# SparkFun-XBee-Serial-Explorer-v12.net
KiCad netlist of a schematic drawn in EAGLE
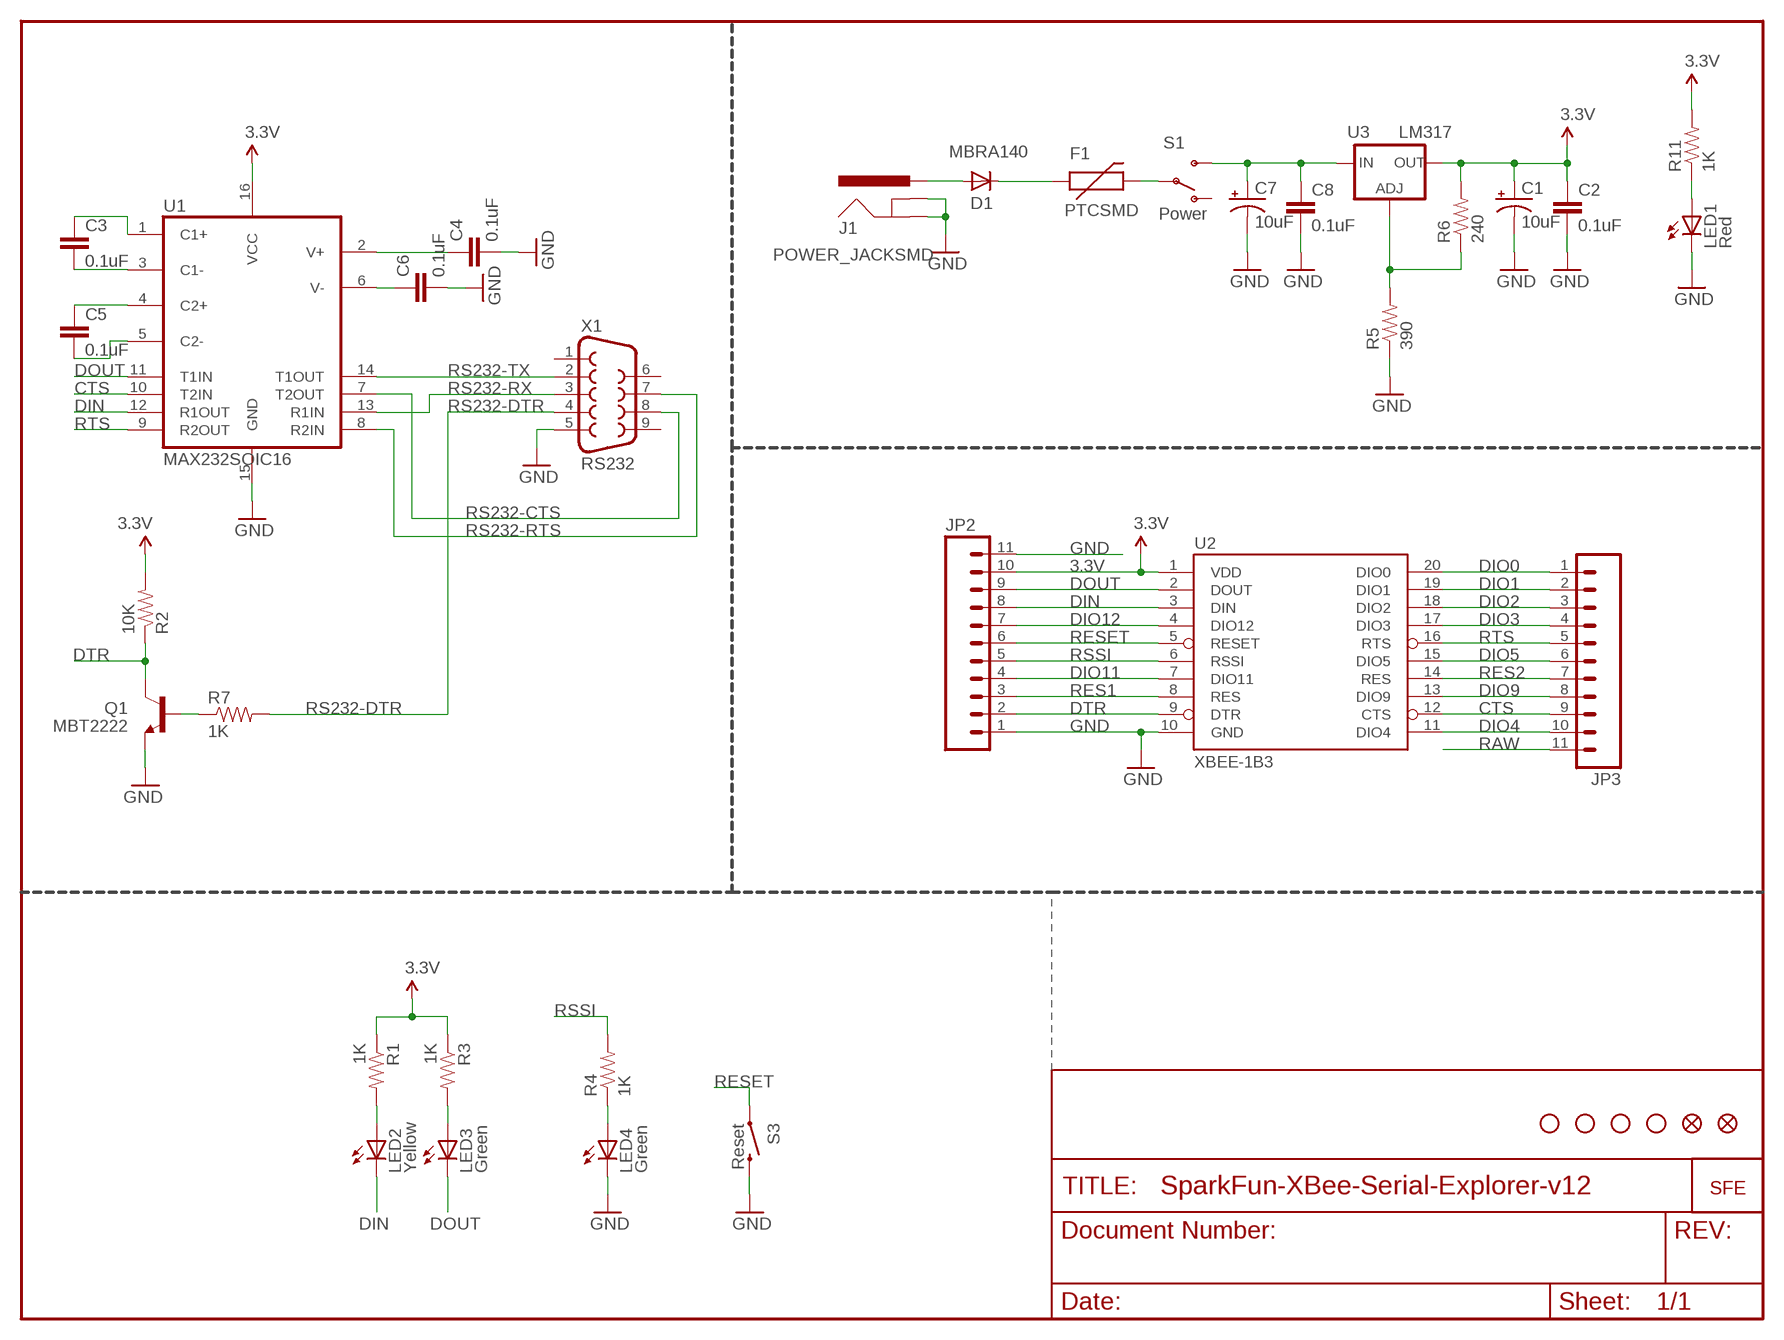
[diagram p0: schematic, sheet 1]

(export (version "E")
  (design (tool "Eeschema 10.0.6"))
  (components
    (comp (ref "C1")
      (value "10uF")
      (footprint "eagle-import:EIA3216")
      (libsource (lib "eagle-import") (part "CAP_POL1206"))
    )
    (comp (ref "C2")
      (value "0.1uF")
      (footprint "eagle-import:C0402")
      (libsource (lib "eagle-import") (part "CAP0402"))
    )
    (comp (ref "C3")
      (value "0.1uF")
      (footprint "eagle-import:C0402")
      (libsource (lib "eagle-import") (part "CAP0402"))
    )
    (comp (ref "C4")
      (value "0.1uF")
      (footprint "eagle-import:C0402")
      (libsource (lib "eagle-import") (part "CAP0402"))
    )
    (comp (ref "C5")
      (value "0.1uF")
      (footprint "eagle-import:C0402")
      (libsource (lib "eagle-import") (part "CAP0402"))
    )
    (comp (ref "C6")
      (value "0.1uF")
      (footprint "eagle-import:C0402")
      (libsource (lib "eagle-import") (part "CAP0402"))
    )
    (comp (ref "C7")
      (value "10uF")
      (footprint "eagle-import:EIA3216")
      (libsource (lib "eagle-import") (part "CAP_POL1206"))
    )
    (comp (ref "C8")
      (value "0.1uF")
      (footprint "eagle-import:C0402")
      (libsource (lib "eagle-import") (part "CAP0402"))
    )
    (comp (ref "D1")
      (value "MBRA140")
      (footprint "eagle-import:SMA-DIODE")
      (libsource (lib "eagle-import") (part "DIODESMA"))
    )
    (comp (ref "F1")
      (value "PTCSMD")
      (footprint "eagle-import:PTC-1206")
      (libsource (lib "eagle-import") (part "PTCSMD"))
    )
    (comp (ref "J1")
      (value "POWER_JACKSMD")
      (footprint "eagle-import:POWER_JACK_SMD")
      (libsource (lib "eagle-import") (part "POWER_JACKSMD"))
    )
    (comp (ref "JP2")
      (value "M11PTH")
      (footprint "eagle-import:1X11")
      (libsource (lib "eagle-import") (part "M11PTH"))
    )
    (comp (ref "JP3")
      (value "M11PTH")
      (footprint "eagle-import:1X11")
      (libsource (lib "eagle-import") (part "M11PTH"))
    )
    (comp (ref "LED1")
      (value "Red")
      (footprint "eagle-import:LED-1206")
      (libsource (lib "eagle-import") (part "LED1206"))
    )
    (comp (ref "LED2")
      (value "Yellow")
      (footprint "eagle-import:LED-1206")
      (libsource (lib "eagle-import") (part "LED1206"))
    )
    (comp (ref "LED3")
      (value "Green")
      (footprint "eagle-import:LED-1206")
      (libsource (lib "eagle-import") (part "LED1206"))
    )
    (comp (ref "LED4")
      (value "Green")
      (footprint "eagle-import:LED-1206")
      (libsource (lib "eagle-import") (part "LED1206"))
    )
    (comp (ref "Q1")
      (value "MBT2222")
      (footprint "eagle-import:SOT23-3")
      (libsource (lib "eagle-import") (part "TRANSISTOR_NPNSOT23-3"))
    )
    (comp (ref "R1")
      (value "1K")
      (footprint "eagle-import:C0402")
      (libsource (lib "eagle-import") (part "RESISTOR0402"))
    )
    (comp (ref "R2")
      (value "10K")
      (footprint "eagle-import:C0402")
      (libsource (lib "eagle-import") (part "RESISTOR0402"))
    )
    (comp (ref "R3")
      (value "1K")
      (footprint "eagle-import:C0402")
      (libsource (lib "eagle-import") (part "RESISTOR0402"))
    )
    (comp (ref "R4")
      (value "1K")
      (footprint "eagle-import:C0402")
      (libsource (lib "eagle-import") (part "RESISTOR0402"))
    )
    (comp (ref "R5")
      (value "390")
      (footprint "eagle-import:C0402")
      (libsource (lib "eagle-import") (part "RESISTOR0402"))
    )
    (comp (ref "R6")
      (value "240")
      (footprint "eagle-import:C0402")
      (libsource (lib "eagle-import") (part "RESISTOR0402"))
    )
    (comp (ref "R7")
      (value "1K")
      (footprint "eagle-import:C0402")
      (libsource (lib "eagle-import") (part "RESISTOR0402"))
    )
    (comp (ref "R11")
      (value "1K")
      (footprint "eagle-import:C0402")
      (libsource (lib "eagle-import") (part "RESISTOR0402"))
    )
    (comp (ref "S1")
      (value "Power")
      (footprint "eagle-import:AYZ0202")
      (libsource (lib "eagle-import") (part "SWITCH-SPSTSMD"))
    )
    (comp (ref "S3")
      (value "Reset")
      (footprint "eagle-import:TACTILE_SWITCH_SMD")
      (libsource (lib "eagle-import") (part "SWITCH-MOMENTARY-2SMD"))
    )
    (comp (ref "U$4")
      (value "LOGO-SFENEW")
      (footprint "eagle-import:SFE-NEW-WEBLOGO")
      (libsource (lib "eagle-import") (part "LOGO-SFENEW"))
    )
    (comp (ref "U$5")
      (value "STAND-OFF")
      (footprint "eagle-import:STAND-OFF")
      (libsource (lib "eagle-import") (part "STAND-OFF"))
    )
    (comp (ref "U$7")
      (value "FIDUCIAL1X2")
      (footprint "eagle-import:FIDUCIAL-1X2")
      (libsource (lib "eagle-import") (part "FIDUCIAL1X2"))
    )
    (comp (ref "U$9")
      (value "STAND-OFF")
      (footprint "eagle-import:STAND-OFF")
      (libsource (lib "eagle-import") (part "STAND-OFF"))
    )
    (comp (ref "U$10")
      (value "STAND-OFF")
      (footprint "eagle-import:STAND-OFF")
      (libsource (lib "eagle-import") (part "STAND-OFF"))
    )
    (comp (ref "U$11")
      (value "STAND-OFF")
      (footprint "eagle-import:STAND-OFF")
      (libsource (lib "eagle-import") (part "STAND-OFF"))
    )
    (comp (ref "U$16")
      (value "FIDUCIAL1X2")
      (footprint "eagle-import:FIDUCIAL-1X2")
      (libsource (lib "eagle-import") (part "FIDUCIAL1X2"))
    )
    (comp (ref "U1")
      (value "MAX232SOIC16")
      (footprint "eagle-import:SO016")
      (libsource (lib "eagle-import") (part "MAX232SOIC16"))
    )
    (comp (ref "U2")
      (value "XBEE-1B3")
      (footprint "eagle-import:XBEE-SMD")
      (libsource (lib "eagle-import") (part "XBEE-1B3"))
    )
    (comp (ref "U3")
      (value "LM317")
      (footprint "eagle-import:SOT223")
      (libsource (lib "eagle-import") (part "V_REG_317SMD"))
    )
    (comp (ref "X1")
      (value "RS232")
      (footprint "eagle-import:DB9")
      (libsource (lib "eagle-import") (part "DB9"))
    )
  )
  (nets
    (net (code "1") (name "/CTS") (class "Default")
      (node (ref "JP3") (pin "9") (pinfunction "9_9") (pintype "passive"))
      (node (ref "U1") (pin "10") (pinfunction "T2IN_10") (pintype "input"))
      (node (ref "U2") (pin "12") (pinfunction "CTS_12") (pintype "output"))
    )
    (net (code "2") (name "/DIN") (class "Default")
      (node (ref "JP2") (pin "8") (pinfunction "8_8") (pintype "passive"))
      (node (ref "LED2") (pin "C") (pinfunction "C_C") (pintype "passive"))
      (node (ref "U1") (pin "12") (pinfunction "R1OUT_12") (pintype "output"))
      (node (ref "U2") (pin "3") (pinfunction "DIN_3") (pintype "input"))
    )
    (net (code "3") (name "/DIO0") (class "Default")
      (node (ref "JP3") (pin "1") (pinfunction "1_1") (pintype "passive"))
      (node (ref "U2") (pin "20") (pinfunction "DIO0_20") (pintype "bidirectional"))
    )
    (net (code "4") (name "/DIO1") (class "Default")
      (node (ref "JP3") (pin "2") (pinfunction "2_2") (pintype "passive"))
      (node (ref "U2") (pin "19") (pinfunction "DIO1_19") (pintype "bidirectional"))
    )
    (net (code "5") (name "/DIO2") (class "Default")
      (node (ref "JP3") (pin "3") (pinfunction "3_3") (pintype "passive"))
      (node (ref "U2") (pin "18") (pinfunction "DIO2_18") (pintype "bidirectional"))
    )
    (net (code "6") (name "/DIO3") (class "Default")
      (node (ref "JP3") (pin "4") (pinfunction "4_4") (pintype "passive"))
      (node (ref "U2") (pin "17") (pinfunction "DIO3_17") (pintype "bidirectional"))
    )
    (net (code "7") (name "/DIO4") (class "Default")
      (node (ref "JP3") (pin "10") (pinfunction "10_10") (pintype "passive"))
      (node (ref "U2") (pin "11") (pinfunction "DIO4_11") (pintype "bidirectional"))
    )
    (net (code "8") (name "/DIO5") (class "Default")
      (node (ref "JP3") (pin "6") (pinfunction "6_6") (pintype "passive"))
      (node (ref "U2") (pin "15") (pinfunction "DIO5_15") (pintype "bidirectional"))
    )
    (net (code "9") (name "/DIO9") (class "Default")
      (node (ref "JP3") (pin "8") (pinfunction "8_8") (pintype "passive"))
      (node (ref "U2") (pin "13") (pinfunction "DIO9_13") (pintype "bidirectional"))
    )
    (net (code "10") (name "/DIO11") (class "Default")
      (node (ref "JP2") (pin "4") (pinfunction "4_4") (pintype "passive"))
      (node (ref "U2") (pin "7") (pinfunction "DIO11_7") (pintype "bidirectional"))
    )
    (net (code "11") (name "/DIO12") (class "Default")
      (node (ref "JP2") (pin "7") (pinfunction "7_7") (pintype "passive"))
      (node (ref "U2") (pin "4") (pinfunction "DIO12_4") (pintype "bidirectional"))
    )
    (net (code "12") (name "/DOUT") (class "Default")
      (node (ref "JP2") (pin "9") (pinfunction "9_9") (pintype "passive"))
      (node (ref "LED3") (pin "C") (pinfunction "C_C") (pintype "passive"))
      (node (ref "U1") (pin "11") (pinfunction "T1IN_11") (pintype "input"))
      (node (ref "U2") (pin "2") (pinfunction "DOUT_2") (pintype "output"))
    )
    (net (code "13") (name "/DTR") (class "Default")
      (node (ref "JP2") (pin "2") (pinfunction "2_2") (pintype "passive"))
      (node (ref "Q1") (pin "3") (pinfunction "C_3") (pintype "passive"))
      (node (ref "R2") (pin "1") (pinfunction "1_1") (pintype "passive"))
      (node (ref "U2") (pin "9") (pinfunction "DTR_9") (pintype "bidirectional"))
    )
    (net (code "14") (name "/RAW") (class "Default")
      (node (ref "C7") (pin "A") (pinfunction "+_A") (pintype "passive"))
      (node (ref "C8") (pin "1") (pinfunction "1_1") (pintype "passive"))
      (node (ref "JP3") (pin "11") (pinfunction "11_11") (pintype "passive"))
      (node (ref "S1") (pin "3") (pinfunction "S_3") (pintype "passive"))
      (node (ref "U3") (pin "3") (pinfunction "IN_3") (pintype "input"))
    )
    (net (code "15") (name "/RES1") (class "Default")
      (node (ref "JP2") (pin "3") (pinfunction "3_3") (pintype "passive"))
      (node (ref "U2") (pin "8") (pinfunction "RES_8") (pintype "bidirectional"))
    )
    (net (code "16") (name "/RES2") (class "Default")
      (node (ref "JP3") (pin "7") (pinfunction "7_7") (pintype "passive"))
      (node (ref "U2") (pin "14") (pinfunction "RES_14") (pintype "bidirectional"))
    )
    (net (code "17") (name "/RESET") (class "Default")
      (node (ref "JP2") (pin "6") (pinfunction "6_6") (pintype "passive"))
      (node (ref "S3") (pin "1") (pinfunction "1_1") (pintype "passive"))
      (node (ref "U2") (pin "5") (pinfunction "RESET_5") (pintype "input"))
    )
    (net (code "18") (name "/RS232-CTS") (class "Default")
      (node (ref "U1") (pin "7") (pinfunction "T2OUT_7") (pintype "output"))
      (node (ref "X1") (pin "8") (pinfunction "8_8") (pintype "passive"))
    )
    (net (code "19") (name "/RS232-DTR") (class "Default")
      (node (ref "R7") (pin "2") (pinfunction "2_2") (pintype "passive"))
      (node (ref "X1") (pin "4") (pinfunction "4_4") (pintype "passive"))
    )
    (net (code "20") (name "/RS232-RTS") (class "Default")
      (node (ref "U1") (pin "8") (pinfunction "R2IN_8") (pintype "input"))
      (node (ref "X1") (pin "7") (pinfunction "7_7") (pintype "passive"))
    )
    (net (code "21") (name "/RS232-RX") (class "Default")
      (node (ref "U1") (pin "13") (pinfunction "R1IN_13") (pintype "input"))
      (node (ref "X1") (pin "3") (pinfunction "3_3") (pintype "passive"))
    )
    (net (code "22") (name "/RS232-TX") (class "Default")
      (node (ref "U1") (pin "14") (pinfunction "T1OUT_14") (pintype "output"))
      (node (ref "X1") (pin "2") (pinfunction "2_2") (pintype "passive"))
    )
    (net (code "23") (name "/RSSI") (class "Default")
      (node (ref "JP2") (pin "5") (pinfunction "5_5") (pintype "passive"))
      (node (ref "R4") (pin "2") (pinfunction "2_2") (pintype "passive"))
      (node (ref "U2") (pin "6") (pinfunction "RSSI_6") (pintype "bidirectional"))
    )
    (net (code "24") (name "/RTS") (class "Default")
      (node (ref "JP3") (pin "5") (pinfunction "5_5") (pintype "passive"))
      (node (ref "U1") (pin "9") (pinfunction "R2OUT_9") (pintype "output"))
      (node (ref "U2") (pin "16") (pinfunction "RTS_16") (pintype "input"))
    )
    (net (code "25") (name "3.3V") (class "Default")
      (node (ref "C1") (pin "A") (pinfunction "+_A") (pintype "passive"))
      (node (ref "C2") (pin "1") (pinfunction "1_1") (pintype "passive"))
      (node (ref "JP2") (pin "10") (pinfunction "10_10") (pintype "passive"))
      (node (ref "R1") (pin "1") (pinfunction "1_1") (pintype "passive"))
      (node (ref "R11") (pin "2") (pinfunction "2_2") (pintype "passive"))
      (node (ref "R2") (pin "2") (pinfunction "2_2") (pintype "passive"))
      (node (ref "R3") (pin "1") (pinfunction "1_1") (pintype "passive"))
      (node (ref "R6") (pin "2") (pinfunction "2_2") (pintype "passive"))
      (node (ref "U1") (pin "16") (pinfunction "VCC_16") (pintype "bidirectional"))
      (node (ref "U2") (pin "1") (pinfunction "VDD_1") (pintype "power_in"))
      (node (ref "U3") (pin "2") (pinfunction "OUT_2") (pintype "output"))
    )
    (net (code "26") (name "GND") (class "Default")
      (node (ref "C1") (pin "C") (pinfunction "-_C") (pintype "passive"))
      (node (ref "C2") (pin "2") (pinfunction "2_2") (pintype "passive"))
      (node (ref "C4") (pin "2") (pinfunction "2_2") (pintype "passive"))
      (node (ref "C6") (pin "2") (pinfunction "2_2") (pintype "passive"))
      (node (ref "C7") (pin "C") (pinfunction "-_C") (pintype "passive"))
      (node (ref "C8") (pin "2") (pinfunction "2_2") (pintype "passive"))
      (node (ref "J1") (pin "GND") (pinfunction "GNDBREAK_GND") (pintype "bidirectional"))
      (node (ref "J1") (pin "P$4") (pinfunction "GND_P$4") (pintype "bidirectional"))
      (node (ref "JP2") (pin "1") (pinfunction "1_1") (pintype "passive"))
      (node (ref "JP2") (pin "11") (pinfunction "11_11") (pintype "passive"))
      (node (ref "LED1") (pin "C") (pinfunction "C_C") (pintype "passive"))
      (node (ref "LED4") (pin "C") (pinfunction "C_C") (pintype "passive"))
      (node (ref "Q1") (pin "2") (pinfunction "E_2") (pintype "passive"))
      (node (ref "R5") (pin "1") (pinfunction "1_1") (pintype "passive"))
      (node (ref "S3") (pin "3") (pinfunction "2_3") (pintype "passive"))
      (node (ref "U1") (pin "15") (pinfunction "GND_15") (pintype "bidirectional"))
      (node (ref "U2") (pin "10") (pinfunction "GND_10") (pintype "power_in"))
      (node (ref "X1") (pin "5") (pinfunction "5_5") (pintype "passive"))
    )
    (net (code "27") (name "Net-(D1-PadC)") (class "Default")
      (node (ref "D1") (pin "C") (pinfunction "C_C") (pintype "passive"))
      (node (ref "F1") (pin "1") (pinfunction "1_1") (pintype "bidirectional"))
    )
    (net (code "28") (name "Net-(J1-PWR)") (class "Default")
      (node (ref "D1") (pin "A") (pinfunction "A_A") (pintype "passive"))
      (node (ref "J1") (pin "VIN0") (pinfunction "PWR_VIN0") (pintype "bidirectional"))
    )
    (net (code "29") (name "Net-(LED1-PadA)") (class "Default")
      (node (ref "LED1") (pin "A") (pinfunction "A_A") (pintype "passive"))
      (node (ref "R11") (pin "1") (pinfunction "1_1") (pintype "passive"))
    )
    (net (code "30") (name "Net-(LED2-PadA)") (class "Default")
      (node (ref "LED2") (pin "A") (pinfunction "A_A") (pintype "passive"))
      (node (ref "R1") (pin "2") (pinfunction "2_2") (pintype "passive"))
    )
    (net (code "31") (name "Net-(LED3-PadA)") (class "Default")
      (node (ref "LED3") (pin "A") (pinfunction "A_A") (pintype "passive"))
      (node (ref "R3") (pin "2") (pinfunction "2_2") (pintype "passive"))
    )
    (net (code "32") (name "Net-(LED4-PadA)") (class "Default")
      (node (ref "LED4") (pin "A") (pinfunction "A_A") (pintype "passive"))
      (node (ref "R4") (pin "1") (pinfunction "1_1") (pintype "passive"))
    )
    (net (code "33") (name "Net-(Q1-B)") (class "Default")
      (node (ref "Q1") (pin "1") (pinfunction "B_1") (pintype "passive"))
      (node (ref "R7") (pin "1") (pinfunction "1_1") (pintype "passive"))
    )
    (net (code "34") (name "Net-(S1-P)") (class "Default")
      (node (ref "F1") (pin "2") (pinfunction "2_2") (pintype "bidirectional"))
      (node (ref "S1") (pin "2") (pinfunction "P_2") (pintype "passive"))
    )
    (net (code "35") (name "Net-(U1-C1+)") (class "Default")
      (node (ref "C3") (pin "1") (pinfunction "1_1") (pintype "passive"))
      (node (ref "U1") (pin "1") (pinfunction "C1+_1") (pintype "bidirectional"))
    )
    (net (code "36") (name "Net-(U1-C1-)") (class "Default")
      (node (ref "C3") (pin "2") (pinfunction "2_2") (pintype "passive"))
      (node (ref "U1") (pin "3") (pinfunction "C1-_3") (pintype "bidirectional"))
    )
    (net (code "37") (name "Net-(U1-C2+)") (class "Default")
      (node (ref "C5") (pin "1") (pinfunction "1_1") (pintype "passive"))
      (node (ref "U1") (pin "4") (pinfunction "C2+_4") (pintype "bidirectional"))
    )
    (net (code "38") (name "Net-(U1-C2-)") (class "Default")
      (node (ref "C5") (pin "2") (pinfunction "2_2") (pintype "passive"))
      (node (ref "U1") (pin "5") (pinfunction "C2-_5") (pintype "bidirectional"))
    )
    (net (code "39") (name "Net-(U1-V+)") (class "Default")
      (node (ref "C4") (pin "1") (pinfunction "1_1") (pintype "passive"))
      (node (ref "U1") (pin "2") (pinfunction "V+_2") (pintype "bidirectional"))
    )
    (net (code "40") (name "Net-(U1-V-)") (class "Default")
      (node (ref "C6") (pin "1") (pinfunction "1_1") (pintype "passive"))
      (node (ref "U1") (pin "6") (pinfunction "V-_6") (pintype "bidirectional"))
    )
    (net (code "41") (name "Net-(U3-ADJ)") (class "Default")
      (node (ref "R5") (pin "2") (pinfunction "2_2") (pintype "passive"))
      (node (ref "R6") (pin "1") (pinfunction "1_1") (pintype "passive"))
      (node (ref "U3") (pin "1") (pinfunction "ADJ_1") (pintype "input"))
    )
    (net (code "42") (name "unconnected-(S1-O-Pad1)") (class "Default")
      (node (ref "S1") (pin "1") (pinfunction "O_1") (pintype "passive"))
    )
    (net (code "43") (name "unconnected-(X1-Pad1)") (class "Default")
      (node (ref "X1") (pin "1") (pinfunction "1_1") (pintype "passive"))
    )
    (net (code "44") (name "unconnected-(X1-Pad6)") (class "Default")
      (node (ref "X1") (pin "6") (pinfunction "6_6") (pintype "passive"))
    )
    (net (code "45") (name "unconnected-(X1-Pad9)") (class "Default")
      (node (ref "X1") (pin "9") (pinfunction "9_9") (pintype "passive"))
    )
  )
)
